# 780-00012-P2_rev4_Sch_M2_Focus_Drive.net
KiCad netlist of a schematic drawn in Altium Designer
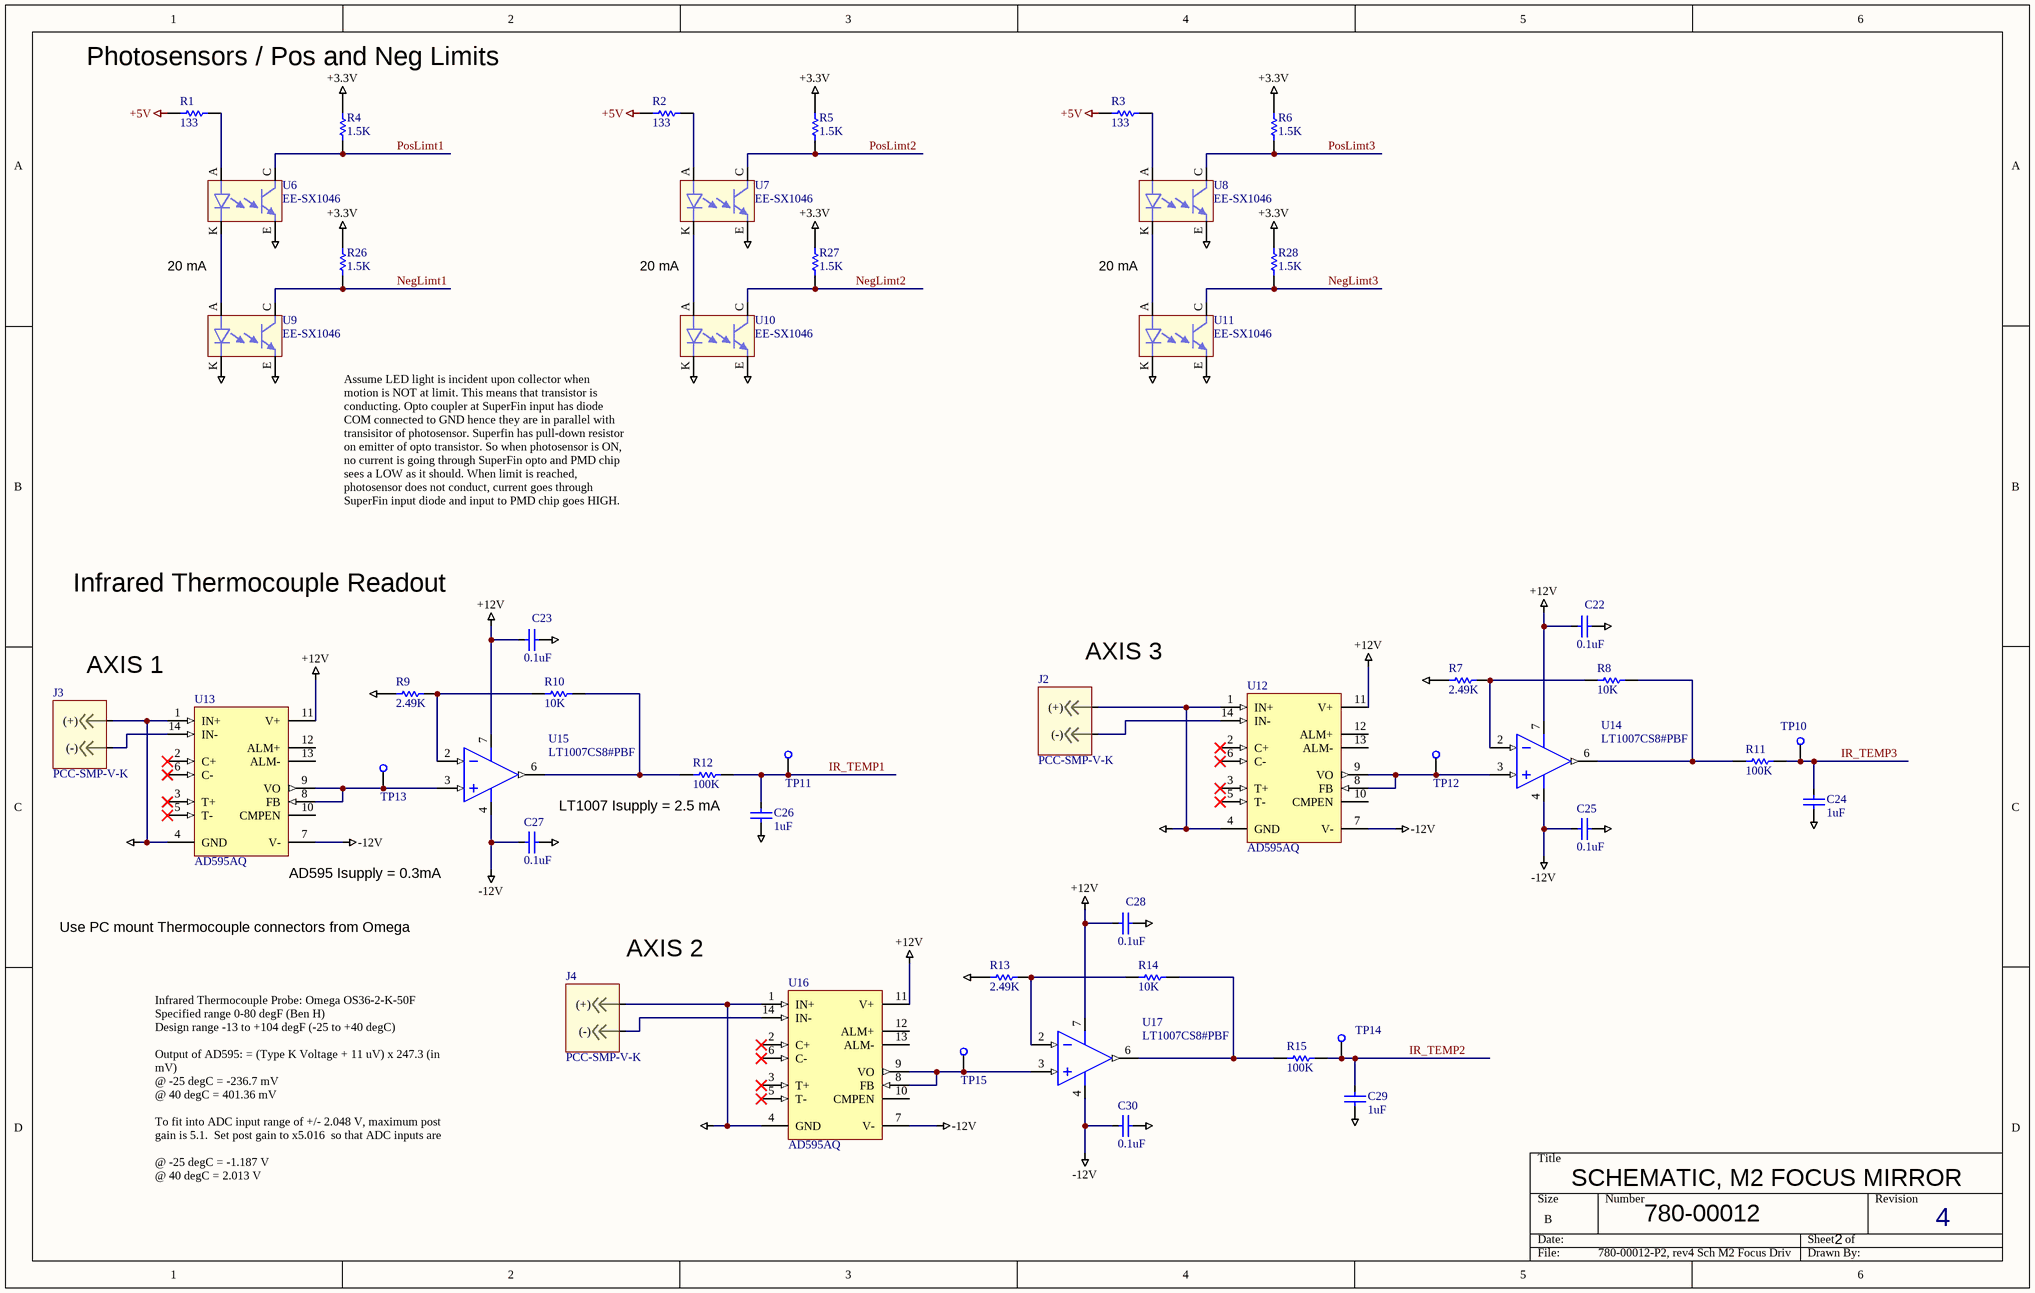
[diagram p0: 780-00012-P2, rev4 Sch M2 Focus Drive.SchDoc]

(export (version "E")
  (design (tool "Eeschema 10.0.6"))
  (components
    (comp (ref "C22")
      (value "0.1uF")
      (footprint "SMD_0805")
      (description "Capacitor")
      (fields (field (name "Comment") "Cap SMD"))
      (libsource (lib "Richs Schematic Components") (part "Cap SMD"))
    )
    (comp (ref "C23")
      (value "0.1uF")
      (footprint "SMD_0805")
      (description "Capacitor")
      (fields (field (name "Comment") "Cap SMD"))
      (libsource (lib "Richs Schematic Components") (part "Cap SMD"))
    )
    (comp (ref "C24")
      (value "1uF")
      (footprint "SMD_0805")
      (description "Capacitor")
      (fields (field (name "Comment") "Cap SMD"))
      (libsource (lib "Richs Schematic Components") (part "Cap SMD"))
    )
    (comp (ref "C25")
      (value "0.1uF")
      (footprint "SMD_0805")
      (description "Capacitor")
      (fields (field (name "Comment") "Cap SMD"))
      (libsource (lib "Richs Schematic Components") (part "Cap SMD"))
    )
    (comp (ref "C26")
      (value "1uF")
      (footprint "SMD_0805")
      (description "Capacitor")
      (fields (field (name "Comment") "Cap SMD"))
      (libsource (lib "Richs Schematic Components") (part "Cap SMD"))
    )
    (comp (ref "C27")
      (value "0.1uF")
      (footprint "SMD_0805")
      (description "Capacitor")
      (fields (field (name "Comment") "Cap SMD"))
      (libsource (lib "Richs Schematic Components") (part "Cap SMD"))
    )
    (comp (ref "C28")
      (value "0.1uF")
      (footprint "SMD_0805")
      (description "Capacitor")
      (fields (field (name "Comment") "Cap SMD"))
      (libsource (lib "Richs Schematic Components") (part "Cap SMD"))
    )
    (comp (ref "C29")
      (value "1uF")
      (footprint "SMD_0805")
      (description "Capacitor")
      (fields (field (name "Comment") "Cap SMD"))
      (libsource (lib "Richs Schematic Components") (part "Cap SMD"))
    )
    (comp (ref "C30")
      (value "0.1uF")
      (footprint "SMD_0805")
      (description "Capacitor")
      (fields (field (name "Comment") "Cap SMD"))
      (libsource (lib "Richs Schematic Components") (part "Cap SMD"))
    )
    (comp (ref "J2")
      (value "PCC-SMP-V-K")
      (footprint "THERMOCOUPLE")
      (description "T/C Conn PCB mount vertical")
      (libsource (lib "Richs Schematic Components") (part "Thermocouple Connector"))
    )
    (comp (ref "J3")
      (value "PCC-SMP-V-K")
      (footprint "THERMOCOUPLE")
      (description "T/C Conn PCB mount vertical")
      (libsource (lib "Richs Schematic Components") (part "Thermocouple Connector"))
    )
    (comp (ref "J4")
      (value "PCC-SMP-V-K")
      (footprint "THERMOCOUPLE")
      (description "T/C Conn PCB mount vertical")
      (libsource (lib "Richs Schematic Components") (part "Thermocouple Connector"))
    )
    (comp (ref "R1")
      (value "133")
      (footprint "SMD_0805")
      (description "Resistor 0805")
      (fields (field (name "MANUFACTURER") "Vishay/Dale") (field (name "Comment") "Res 0805"))
      (libsource (lib "Richs Schematic Components") (part "Res SMD"))
    )
    (comp (ref "R2")
      (value "133")
      (footprint "SMD_0805")
      (description "Resistor 0805")
      (fields (field (name "MANUFACTURER") "Vishay/Dale") (field (name "Comment") "Res 0805"))
      (libsource (lib "Richs Schematic Components") (part "Res SMD"))
    )
    (comp (ref "R3")
      (value "133")
      (footprint "SMD_0805")
      (description "Resistor 0805")
      (fields (field (name "MANUFACTURER") "Vishay/Dale") (field (name "Comment") "Res 0805"))
      (libsource (lib "Richs Schematic Components") (part "Res SMD"))
    )
    (comp (ref "R4")
      (value "1.5K")
      (footprint "SMD_0805")
      (description "Resistor 0805")
      (fields (field (name "MANUFACTURER") "Vishay/Dale") (field (name "Comment") "Res 0805"))
      (libsource (lib "Richs Schematic Components") (part "Res SMD"))
    )
    (comp (ref "R5")
      (value "1.5K")
      (footprint "SMD_0805")
      (description "Resistor 0805")
      (fields (field (name "MANUFACTURER") "Vishay/Dale") (field (name "Comment") "Res 0805"))
      (libsource (lib "Richs Schematic Components") (part "Res SMD"))
    )
    (comp (ref "R6")
      (value "1.5K")
      (footprint "SMD_0805")
      (description "Resistor 0805")
      (fields (field (name "MANUFACTURER") "Vishay/Dale") (field (name "Comment") "Res 0805"))
      (libsource (lib "Richs Schematic Components") (part "Res SMD"))
    )
    (comp (ref "R7")
      (value "2.49K")
      (footprint "SMD_0805")
      (description "Resistor 0805")
      (fields (field (name "MANUFACTURER") "Vishay/Dale") (field (name "Comment") "Res 0805"))
      (libsource (lib "Richs Schematic Components") (part "Res SMD"))
    )
    (comp (ref "R8")
      (value "10K")
      (footprint "SMD_0805")
      (description "Resistor 0805")
      (fields (field (name "MANUFACTURER") "Vishay/Dale") (field (name "Comment") "Res 0805"))
      (libsource (lib "Richs Schematic Components") (part "Res SMD"))
    )
    (comp (ref "R9")
      (value "2.49K")
      (footprint "SMD_0805")
      (description "Resistor 0805")
      (fields (field (name "MANUFACTURER") "Vishay/Dale") (field (name "Comment") "Res 0805"))
      (libsource (lib "Richs Schematic Components") (part "Res SMD"))
    )
    (comp (ref "R10")
      (value "10K")
      (footprint "SMD_0805")
      (description "Resistor 0805")
      (fields (field (name "MANUFACTURER") "Vishay/Dale") (field (name "Comment") "Res 0805"))
      (libsource (lib "Richs Schematic Components") (part "Res SMD"))
    )
    (comp (ref "R11")
      (value "100K")
      (footprint "SMD_0805")
      (description "Resistor 0805")
      (fields (field (name "MANUFACTURER") "Vishay/Dale") (field (name "Comment") "Res 0805"))
      (libsource (lib "Richs Schematic Components") (part "Res SMD"))
    )
    (comp (ref "R12")
      (value "100K")
      (footprint "SMD_0805")
      (description "Resistor 0805")
      (fields (field (name "MANUFACTURER") "Vishay/Dale") (field (name "Comment") "Res 0805"))
      (libsource (lib "Richs Schematic Components") (part "Res SMD"))
    )
    (comp (ref "R13")
      (value "2.49K")
      (footprint "SMD_0805")
      (description "Resistor 0805")
      (fields (field (name "MANUFACTURER") "Vishay/Dale") (field (name "Comment") "Res 0805"))
      (libsource (lib "Richs Schematic Components") (part "Res SMD"))
    )
    (comp (ref "R14")
      (value "10K")
      (footprint "SMD_0805")
      (description "Resistor 0805")
      (fields (field (name "MANUFACTURER") "Vishay/Dale") (field (name "Comment") "Res 0805"))
      (libsource (lib "Richs Schematic Components") (part "Res SMD"))
    )
    (comp (ref "R15")
      (value "100K")
      (footprint "SMD_0805")
      (description "Resistor 0805")
      (fields (field (name "MANUFACTURER") "Vishay/Dale") (field (name "Comment") "Res 0805"))
      (libsource (lib "Richs Schematic Components") (part "Res SMD"))
    )
    (comp (ref "R26")
      (value "1.5K")
      (footprint "SMD_0805")
      (description "Resistor 0805")
      (fields (field (name "MANUFACTURER") "Vishay/Dale") (field (name "Comment") "Res 0805"))
      (libsource (lib "Richs Schematic Components") (part "Res SMD"))
    )
    (comp (ref "R27")
      (value "1.5K")
      (footprint "SMD_0805")
      (description "Resistor 0805")
      (fields (field (name "MANUFACTURER") "Vishay/Dale") (field (name "Comment") "Res 0805"))
      (libsource (lib "Richs Schematic Components") (part "Res SMD"))
    )
    (comp (ref "R28")
      (value "1.5K")
      (footprint "SMD_0805")
      (description "Resistor 0805")
      (fields (field (name "MANUFACTURER") "Vishay/Dale") (field (name "Comment") "Res 0805"))
      (libsource (lib "Richs Schematic Components") (part "Res SMD"))
    )
    (comp (ref "TP10")
      (value "Test Point SMD")
      (footprint "SMD_TEST POINT")
      (description "SMD loop test point")
      (libsource (lib "Richs Schematic Components") (part "Test Point SMD"))
    )
    (comp (ref "TP11")
      (value "Test Point SMD")
      (footprint "SMD_TEST POINT")
      (description "SMD loop test point")
      (libsource (lib "Richs Schematic Components") (part "Test Point SMD"))
    )
    (comp (ref "TP12")
      (value "Test Point SMD")
      (footprint "SMD_TEST POINT")
      (description "SMD loop test point")
      (libsource (lib "Richs Schematic Components") (part "Test Point SMD"))
    )
    (comp (ref "TP13")
      (value "Test Point SMD")
      (footprint "SMD_TEST POINT")
      (description "SMD loop test point")
      (libsource (lib "Richs Schematic Components") (part "Test Point SMD"))
    )
    (comp (ref "TP14")
      (value "Test Point SMD")
      (footprint "SMD_TEST POINT")
      (description "SMD loop test point")
      (libsource (lib "Richs Schematic Components") (part "Test Point SMD"))
    )
    (comp (ref "TP15")
      (value "Test Point SMD")
      (footprint "SMD_TEST POINT")
      (description "SMD loop test point")
      (libsource (lib "Richs Schematic Components") (part "Test Point SMD"))
    )
    (comp (ref "U6")
      (value "EE-SX1046")
      (footprint "Photo-sensor")
      (description "Omron EE-SX1046")
      (libsource (lib "Richs Schematic Components") (part "Photo-sensor"))
    )
    (comp (ref "U7")
      (value "EE-SX1046")
      (footprint "Photo-sensor")
      (description "Omron EE-SX1046")
      (libsource (lib "Richs Schematic Components") (part "Photo-sensor"))
    )
    (comp (ref "U8")
      (value "EE-SX1046")
      (footprint "Photo-sensor")
      (description "Omron EE-SX1046")
      (libsource (lib "Richs Schematic Components") (part "Photo-sensor"))
    )
    (comp (ref "U9")
      (value "EE-SX1046")
      (footprint "Photo-sensor")
      (description "Omron EE-SX1046")
      (libsource (lib "Richs Schematic Components") (part "Photo-sensor"))
    )
    (comp (ref "U10")
      (value "EE-SX1046")
      (footprint "Photo-sensor")
      (description "Omron EE-SX1046")
      (libsource (lib "Richs Schematic Components") (part "Photo-sensor"))
    )
    (comp (ref "U11")
      (value "EE-SX1046")
      (footprint "Photo-sensor")
      (description "Omron EE-SX1046")
      (libsource (lib "Richs Schematic Components") (part "Photo-sensor"))
    )
    (comp (ref "U12")
      (value "AD595AQ")
      (footprint "Q-14_A")
      (description "Monolithic Thermocouple Amplifier with Cold Junction Compensation")
      (fields (field (name "MANUFACTURER") "Analog Devices"))
      (libsource (lib "AD Thermocouple Amplifier") (part "AD595AQ"))
    )
    (comp (ref "U13")
      (value "AD595AQ")
      (footprint "Q-14_A")
      (description "Monolithic Thermocouple Amplifier with Cold Junction Compensation")
      (fields (field (name "MANUFACTURER") "Analog Devices"))
      (libsource (lib "AD Thermocouple Amplifier") (part "AD595AQ"))
    )
    (comp (ref "U14")
      (value "LT1007CS8#PBF")
      (footprint "S8_M")
      (description "Low Noise BJT input opamp")
      (fields (field (name "MANUFACTURER") "Linear Tech"))
      (libsource (lib "Richs Schematic Components") (part "LT1007CS8#PBF"))
    )
    (comp (ref "U15")
      (value "LT1007CS8#PBF")
      (footprint "S8_M")
      (description "Low Noise BJT input opamp")
      (fields (field (name "MANUFACTURER") "Linear Tech"))
      (libsource (lib "Richs Schematic Components") (part "LT1007CS8#PBF"))
    )
    (comp (ref "U16")
      (value "AD595AQ")
      (footprint "Q-14_A")
      (description "Monolithic Thermocouple Amplifier with Cold Junction Compensation")
      (fields (field (name "MANUFACTURER") "Analog Devices"))
      (libsource (lib "AD Thermocouple Amplifier") (part "AD595AQ"))
    )
    (comp (ref "U17")
      (value "LT1007CS8#PBF")
      (footprint "S8_M")
      (description "Low Noise BJT input opamp")
      (fields (field (name "MANUFACTURER") "Linear Tech"))
      (libsource (lib "Richs Schematic Components") (part "LT1007CS8#PBF"))
    )
  )
  (nets
    (net (code "1") (name "+3.3V") (class "Default")
      (node (ref "R26") (pin "2") (pinfunction "2_2") (pintype "passive"))
      (node (ref "R27") (pin "2") (pinfunction "2_2") (pintype "passive"))
      (node (ref "R28") (pin "2") (pinfunction "2_2") (pintype "passive"))
      (node (ref "R4") (pin "2") (pinfunction "2_2") (pintype "passive"))
      (node (ref "R5") (pin "2") (pinfunction "2_2") (pintype "passive"))
      (node (ref "R6") (pin "2") (pinfunction "2_2") (pintype "passive"))
    )
    (net (code "2") (name "+5V") (class "Default")
      (node (ref "R1") (pin "2") (pinfunction "2_2") (pintype "passive"))
      (node (ref "R2") (pin "2") (pinfunction "2_2") (pintype "passive"))
      (node (ref "R3") (pin "2") (pinfunction "2_2") (pintype "passive"))
    )
    (net (code "3") (name "+12V") (class "Default")
      (node (ref "C22") (pin "2") (pinfunction "2_2") (pintype "passive"))
      (node (ref "C23") (pin "2") (pinfunction "2_2") (pintype "passive"))
      (node (ref "C28") (pin "2") (pinfunction "2_2") (pintype "passive"))
      (node (ref "U12") (pin "11") (pinfunction "V+_11") (pintype "power_in"))
      (node (ref "U13") (pin "11") (pinfunction "V+_11") (pintype "power_in"))
      (node (ref "U14") (pin "7") (pinfunction "V+_7") (pintype "power_in"))
      (node (ref "U15") (pin "7") (pinfunction "V+_7") (pintype "power_in"))
      (node (ref "U16") (pin "11") (pinfunction "V+_11") (pintype "power_in"))
      (node (ref "U17") (pin "7") (pinfunction "V+_7") (pintype "power_in"))
    )
    (net (code "4") (name "-12V") (class "Default")
      (node (ref "C25") (pin "2") (pinfunction "2_2") (pintype "passive"))
      (node (ref "C27") (pin "2") (pinfunction "2_2") (pintype "passive"))
      (node (ref "C30") (pin "2") (pinfunction "2_2") (pintype "passive"))
      (node (ref "U12") (pin "7") (pinfunction "V-_7") (pintype "power_in"))
      (node (ref "U13") (pin "7") (pinfunction "V-_7") (pintype "power_in"))
      (node (ref "U14") (pin "4") (pinfunction "V-_4") (pintype "power_in"))
      (node (ref "U15") (pin "4") (pinfunction "V-_4") (pintype "power_in"))
      (node (ref "U16") (pin "7") (pinfunction "V-_7") (pintype "power_in"))
      (node (ref "U17") (pin "4") (pinfunction "V-_4") (pintype "power_in"))
    )
    (net (code "5") (name "/IR_TEMP1") (class "Default")
      (node (ref "C26") (pin "2") (pinfunction "2_2") (pintype "passive"))
      (node (ref "R12") (pin "2") (pinfunction "2_2") (pintype "passive"))
      (node (ref "TP11") (pin "1") (pinfunction "TP_1") (pintype "passive"))
    )
    (net (code "6") (name "/IR_TEMP2") (class "Default")
      (node (ref "C29") (pin "2") (pinfunction "2_2") (pintype "passive"))
      (node (ref "R15") (pin "2") (pinfunction "2_2") (pintype "passive"))
      (node (ref "TP14") (pin "1") (pinfunction "TP_1") (pintype "passive"))
    )
    (net (code "7") (name "/IR_TEMP3") (class "Default")
      (node (ref "C24") (pin "2") (pinfunction "2_2") (pintype "passive"))
      (node (ref "R11") (pin "2") (pinfunction "2_2") (pintype "passive"))
      (node (ref "TP10") (pin "1") (pinfunction "TP_1") (pintype "passive"))
    )
    (net (code "8") (name "/NegLimt1") (class "Default")
      (node (ref "R26") (pin "1") (pinfunction "1_1") (pintype "passive"))
      (node (ref "U9") (pin "C") (pinfunction "collector_C") (pintype "passive"))
    )
    (net (code "9") (name "/NegLimt2") (class "Default")
      (node (ref "R27") (pin "1") (pinfunction "1_1") (pintype "passive"))
      (node (ref "U10") (pin "C") (pinfunction "collector_C") (pintype "passive"))
    )
    (net (code "10") (name "/NegLimt3") (class "Default")
      (node (ref "R28") (pin "1") (pinfunction "1_1") (pintype "passive"))
      (node (ref "U11") (pin "C") (pinfunction "collector_C") (pintype "passive"))
    )
    (net (code "11") (name "/PosLimt1") (class "Default")
      (node (ref "R4") (pin "1") (pinfunction "1_1") (pintype "passive"))
      (node (ref "U6") (pin "C") (pinfunction "collector_C") (pintype "passive"))
    )
    (net (code "12") (name "/PosLimt2") (class "Default")
      (node (ref "R5") (pin "1") (pinfunction "1_1") (pintype "passive"))
      (node (ref "U7") (pin "C") (pinfunction "collector_C") (pintype "passive"))
    )
    (net (code "13") (name "/PosLimt3") (class "Default")
      (node (ref "R6") (pin "1") (pinfunction "1_1") (pintype "passive"))
      (node (ref "U8") (pin "C") (pinfunction "collector_C") (pintype "passive"))
    )
    (net (code "14") (name "GND") (class "Default")
      (node (ref "C22") (pin "1") (pinfunction "1_1") (pintype "passive"))
      (node (ref "C23") (pin "1") (pinfunction "1_1") (pintype "passive"))
      (node (ref "C24") (pin "1") (pinfunction "1_1") (pintype "passive"))
      (node (ref "C25") (pin "1") (pinfunction "1_1") (pintype "passive"))
      (node (ref "C26") (pin "1") (pinfunction "1_1") (pintype "passive"))
      (node (ref "C27") (pin "1") (pinfunction "1_1") (pintype "passive"))
      (node (ref "C28") (pin "1") (pinfunction "1_1") (pintype "passive"))
      (node (ref "C29") (pin "1") (pinfunction "1_1") (pintype "passive"))
      (node (ref "C30") (pin "1") (pinfunction "1_1") (pintype "passive"))
      (node (ref "J2") (pin "1") (pinfunction "(+)_1") (pintype "passive"))
      (node (ref "J3") (pin "1") (pinfunction "(+)_1") (pintype "passive"))
      (node (ref "J4") (pin "1") (pinfunction "(+)_1") (pintype "passive"))
      (node (ref "R13") (pin "1") (pinfunction "1_1") (pintype "passive"))
      (node (ref "R7") (pin "1") (pinfunction "1_1") (pintype "passive"))
      (node (ref "R9") (pin "1") (pinfunction "1_1") (pintype "passive"))
      (node (ref "U10") (pin "E") (pinfunction "emitter_E") (pintype "passive"))
      (node (ref "U10") (pin "K") (pinfunction "cathode_K") (pintype "passive"))
      (node (ref "U11") (pin "E") (pinfunction "emitter_E") (pintype "passive"))
      (node (ref "U11") (pin "K") (pinfunction "cathode_K") (pintype "passive"))
      (node (ref "U12") (pin "1") (pinfunction "IN+_1") (pintype "input"))
      (node (ref "U12") (pin "4") (pinfunction "GND_4") (pintype "power_in"))
      (node (ref "U13") (pin "1") (pinfunction "IN+_1") (pintype "input"))
      (node (ref "U13") (pin "4") (pinfunction "GND_4") (pintype "power_in"))
      (node (ref "U16") (pin "1") (pinfunction "IN+_1") (pintype "input"))
      (node (ref "U16") (pin "4") (pinfunction "GND_4") (pintype "power_in"))
      (node (ref "U6") (pin "E") (pinfunction "emitter_E") (pintype "passive"))
      (node (ref "U7") (pin "E") (pinfunction "emitter_E") (pintype "passive"))
      (node (ref "U8") (pin "E") (pinfunction "emitter_E") (pintype "passive"))
      (node (ref "U9") (pin "E") (pinfunction "emitter_E") (pintype "passive"))
      (node (ref "U9") (pin "K") (pinfunction "cathode_K") (pintype "passive"))
    )
    (net (code "15") (name "Net-(J2-(-))") (class "Default")
      (node (ref "J2") (pin "2") (pinfunction "(-)_2") (pintype "passive"))
      (node (ref "U12") (pin "14") (pinfunction "IN-_14") (pintype "input"))
    )
    (net (code "16") (name "Net-(J3-(-))") (class "Default")
      (node (ref "J3") (pin "2") (pinfunction "(-)_2") (pintype "passive"))
      (node (ref "U13") (pin "14") (pinfunction "IN-_14") (pintype "input"))
    )
    (net (code "17") (name "Net-(J4-(-))") (class "Default")
      (node (ref "J4") (pin "2") (pinfunction "(-)_2") (pintype "passive"))
      (node (ref "U16") (pin "14") (pinfunction "IN-_14") (pintype "input"))
    )
    (net (code "18") (name "Net-(TP12-TP)") (class "Default")
      (node (ref "TP12") (pin "1") (pinfunction "TP_1") (pintype "passive"))
      (node (ref "U12") (pin "8") (pinfunction "FB_8") (pintype "input"))
      (node (ref "U12") (pin "9") (pinfunction "VO_9") (pintype "output"))
      (node (ref "U14") (pin "3") (pinfunction "IN+_3") (pintype "input"))
    )
    (net (code "19") (name "Net-(TP13-TP)") (class "Default")
      (node (ref "TP13") (pin "1") (pinfunction "TP_1") (pintype "passive"))
      (node (ref "U13") (pin "8") (pinfunction "FB_8") (pintype "input"))
      (node (ref "U13") (pin "9") (pinfunction "VO_9") (pintype "output"))
      (node (ref "U15") (pin "3") (pinfunction "IN+_3") (pintype "input"))
    )
    (net (code "20") (name "Net-(TP15-TP)") (class "Default")
      (node (ref "TP15") (pin "1") (pinfunction "TP_1") (pintype "passive"))
      (node (ref "U16") (pin "8") (pinfunction "FB_8") (pintype "input"))
      (node (ref "U16") (pin "9") (pinfunction "VO_9") (pintype "output"))
      (node (ref "U17") (pin "3") (pinfunction "IN+_3") (pintype "input"))
    )
    (net (code "21") (name "Net-(U6-anode)") (class "Default")
      (node (ref "R1") (pin "1") (pinfunction "1_1") (pintype "passive"))
      (node (ref "U6") (pin "A") (pinfunction "anode_A") (pintype "passive"))
    )
    (net (code "22") (name "Net-(U6-cathode)") (class "Default")
      (node (ref "U6") (pin "K") (pinfunction "cathode_K") (pintype "passive"))
      (node (ref "U9") (pin "A") (pinfunction "anode_A") (pintype "passive"))
    )
    (net (code "23") (name "Net-(U7-anode)") (class "Default")
      (node (ref "R2") (pin "1") (pinfunction "1_1") (pintype "passive"))
      (node (ref "U7") (pin "A") (pinfunction "anode_A") (pintype "passive"))
    )
    (net (code "24") (name "Net-(U8-anode)") (class "Default")
      (node (ref "R3") (pin "1") (pinfunction "1_1") (pintype "passive"))
      (node (ref "U8") (pin "A") (pinfunction "anode_A") (pintype "passive"))
    )
    (net (code "25") (name "Net-(U10-anode)") (class "Default")
      (node (ref "U10") (pin "A") (pinfunction "anode_A") (pintype "passive"))
      (node (ref "U7") (pin "K") (pinfunction "cathode_K") (pintype "passive"))
    )
    (net (code "26") (name "Net-(U11-anode)") (class "Default")
      (node (ref "U11") (pin "A") (pinfunction "anode_A") (pintype "passive"))
      (node (ref "U8") (pin "K") (pinfunction "cathode_K") (pintype "passive"))
    )
    (net (code "27") (name "Net-(U14-IN-)") (class "Default")
      (node (ref "R7") (pin "2") (pinfunction "2_2") (pintype "passive"))
      (node (ref "R8") (pin "1") (pinfunction "1_1") (pintype "passive"))
      (node (ref "U14") (pin "2") (pinfunction "IN-_2") (pintype "input"))
    )
    (net (code "28") (name "Net-(U14-OUT)") (class "Default")
      (node (ref "R11") (pin "1") (pinfunction "1_1") (pintype "passive"))
      (node (ref "R8") (pin "2") (pinfunction "2_2") (pintype "passive"))
      (node (ref "U14") (pin "6") (pinfunction "OUT_6") (pintype "output"))
    )
    (net (code "29") (name "Net-(U15-IN-)") (class "Default")
      (node (ref "R10") (pin "1") (pinfunction "1_1") (pintype "passive"))
      (node (ref "R9") (pin "2") (pinfunction "2_2") (pintype "passive"))
      (node (ref "U15") (pin "2") (pinfunction "IN-_2") (pintype "input"))
    )
    (net (code "30") (name "Net-(U15-OUT)") (class "Default")
      (node (ref "R10") (pin "2") (pinfunction "2_2") (pintype "passive"))
      (node (ref "R12") (pin "1") (pinfunction "1_1") (pintype "passive"))
      (node (ref "U15") (pin "6") (pinfunction "OUT_6") (pintype "output"))
    )
    (net (code "31") (name "Net-(U17-IN-)") (class "Default")
      (node (ref "R13") (pin "2") (pinfunction "2_2") (pintype "passive"))
      (node (ref "R14") (pin "1") (pinfunction "1_1") (pintype "passive"))
      (node (ref "U17") (pin "2") (pinfunction "IN-_2") (pintype "input"))
    )
    (net (code "32") (name "Net-(U17-OUT)") (class "Default")
      (node (ref "R14") (pin "2") (pinfunction "2_2") (pintype "passive"))
      (node (ref "R15") (pin "1") (pinfunction "1_1") (pintype "passive"))
      (node (ref "U17") (pin "6") (pinfunction "OUT_6") (pintype "output"))
    )
    (net (code "33") (name "unconnected-(U12-ALM+-Pad12)") (class "Default")
      (node (ref "U12") (pin "12") (pinfunction "ALM+_12") (pintype "passive"))
    )
    (net (code "34") (name "unconnected-(U12-ALM--Pad13)") (class "Default")
      (node (ref "U12") (pin "13") (pinfunction "ALM-_13") (pintype "passive"))
    )
    (net (code "35") (name "unconnected-(U12-C+-Pad2)") (class "Default")
      (node (ref "U12") (pin "2") (pinfunction "C+_2") (pintype "input+no_connect"))
    )
    (net (code "36") (name "unconnected-(U12-C--Pad6)") (class "Default")
      (node (ref "U12") (pin "6") (pinfunction "C-_6") (pintype "input+no_connect"))
    )
    (net (code "37") (name "unconnected-(U12-CMPEN-Pad10)") (class "Default")
      (node (ref "U12") (pin "10") (pinfunction "CMPEN_10") (pintype "passive"))
    )
    (net (code "38") (name "unconnected-(U12-T+-Pad3)") (class "Default")
      (node (ref "U12") (pin "3") (pinfunction "T+_3") (pintype "input+no_connect"))
    )
    (net (code "39") (name "unconnected-(U12-T--Pad5)") (class "Default")
      (node (ref "U12") (pin "5") (pinfunction "T-_5") (pintype "input+no_connect"))
    )
    (net (code "40") (name "unconnected-(U13-ALM+-Pad12)") (class "Default")
      (node (ref "U13") (pin "12") (pinfunction "ALM+_12") (pintype "passive"))
    )
    (net (code "41") (name "unconnected-(U13-ALM--Pad13)") (class "Default")
      (node (ref "U13") (pin "13") (pinfunction "ALM-_13") (pintype "passive"))
    )
    (net (code "42") (name "unconnected-(U13-C+-Pad2)") (class "Default")
      (node (ref "U13") (pin "2") (pinfunction "C+_2") (pintype "input+no_connect"))
    )
    (net (code "43") (name "unconnected-(U13-C--Pad6)") (class "Default")
      (node (ref "U13") (pin "6") (pinfunction "C-_6") (pintype "input+no_connect"))
    )
    (net (code "44") (name "unconnected-(U13-CMPEN-Pad10)") (class "Default")
      (node (ref "U13") (pin "10") (pinfunction "CMPEN_10") (pintype "passive"))
    )
    (net (code "45") (name "unconnected-(U13-T+-Pad3)") (class "Default")
      (node (ref "U13") (pin "3") (pinfunction "T+_3") (pintype "input+no_connect"))
    )
    (net (code "46") (name "unconnected-(U13-T--Pad5)") (class "Default")
      (node (ref "U13") (pin "5") (pinfunction "T-_5") (pintype "input+no_connect"))
    )
    (net (code "47") (name "unconnected-(U14-NC-Pad5)") (class "Default")
      (node (ref "U14") (pin "5") (pinfunction "NC_5") (pintype "passive"))
    )
    (net (code "48") (name "unconnected-(U14-VOSTRIM-Pad1)") (class "Default")
      (node (ref "U14") (pin "1") (pinfunction "VOSTRIM_1") (pintype "passive"))
    )
    (net (code "49") (name "unconnected-(U14-VOSTRIM-Pad8)") (class "Default")
      (node (ref "U14") (pin "8") (pinfunction "VOSTRIM_8") (pintype "passive"))
    )
    (net (code "50") (name "unconnected-(U15-NC-Pad5)") (class "Default")
      (node (ref "U15") (pin "5") (pinfunction "NC_5") (pintype "passive"))
    )
    (net (code "51") (name "unconnected-(U15-VOSTRIM-Pad1)") (class "Default")
      (node (ref "U15") (pin "1") (pinfunction "VOSTRIM_1") (pintype "passive"))
    )
    (net (code "52") (name "unconnected-(U15-VOSTRIM-Pad8)") (class "Default")
      (node (ref "U15") (pin "8") (pinfunction "VOSTRIM_8") (pintype "passive"))
    )
    (net (code "53") (name "unconnected-(U16-ALM+-Pad12)") (class "Default")
      (node (ref "U16") (pin "12") (pinfunction "ALM+_12") (pintype "passive"))
    )
    (net (code "54") (name "unconnected-(U16-ALM--Pad13)") (class "Default")
      (node (ref "U16") (pin "13") (pinfunction "ALM-_13") (pintype "passive"))
    )
    (net (code "55") (name "unconnected-(U16-C+-Pad2)") (class "Default")
      (node (ref "U16") (pin "2") (pinfunction "C+_2") (pintype "input+no_connect"))
    )
    (net (code "56") (name "unconnected-(U16-C--Pad6)") (class "Default")
      (node (ref "U16") (pin "6") (pinfunction "C-_6") (pintype "input+no_connect"))
    )
    (net (code "57") (name "unconnected-(U16-CMPEN-Pad10)") (class "Default")
      (node (ref "U16") (pin "10") (pinfunction "CMPEN_10") (pintype "passive"))
    )
    (net (code "58") (name "unconnected-(U16-T+-Pad3)") (class "Default")
      (node (ref "U16") (pin "3") (pinfunction "T+_3") (pintype "input+no_connect"))
    )
    (net (code "59") (name "unconnected-(U16-T--Pad5)") (class "Default")
      (node (ref "U16") (pin "5") (pinfunction "T-_5") (pintype "input+no_connect"))
    )
    (net (code "60") (name "unconnected-(U17-NC-Pad5)") (class "Default")
      (node (ref "U17") (pin "5") (pinfunction "NC_5") (pintype "passive"))
    )
    (net (code "61") (name "unconnected-(U17-VOSTRIM-Pad1)") (class "Default")
      (node (ref "U17") (pin "1") (pinfunction "VOSTRIM_1") (pintype "passive"))
    )
    (net (code "62") (name "unconnected-(U17-VOSTRIM-Pad8)") (class "Default")
      (node (ref "U17") (pin "8") (pinfunction "VOSTRIM_8") (pintype "passive"))
    )
  )
)
